# PCC_hat3.net
KiCad netlist of a schematic drawn in EAGLE
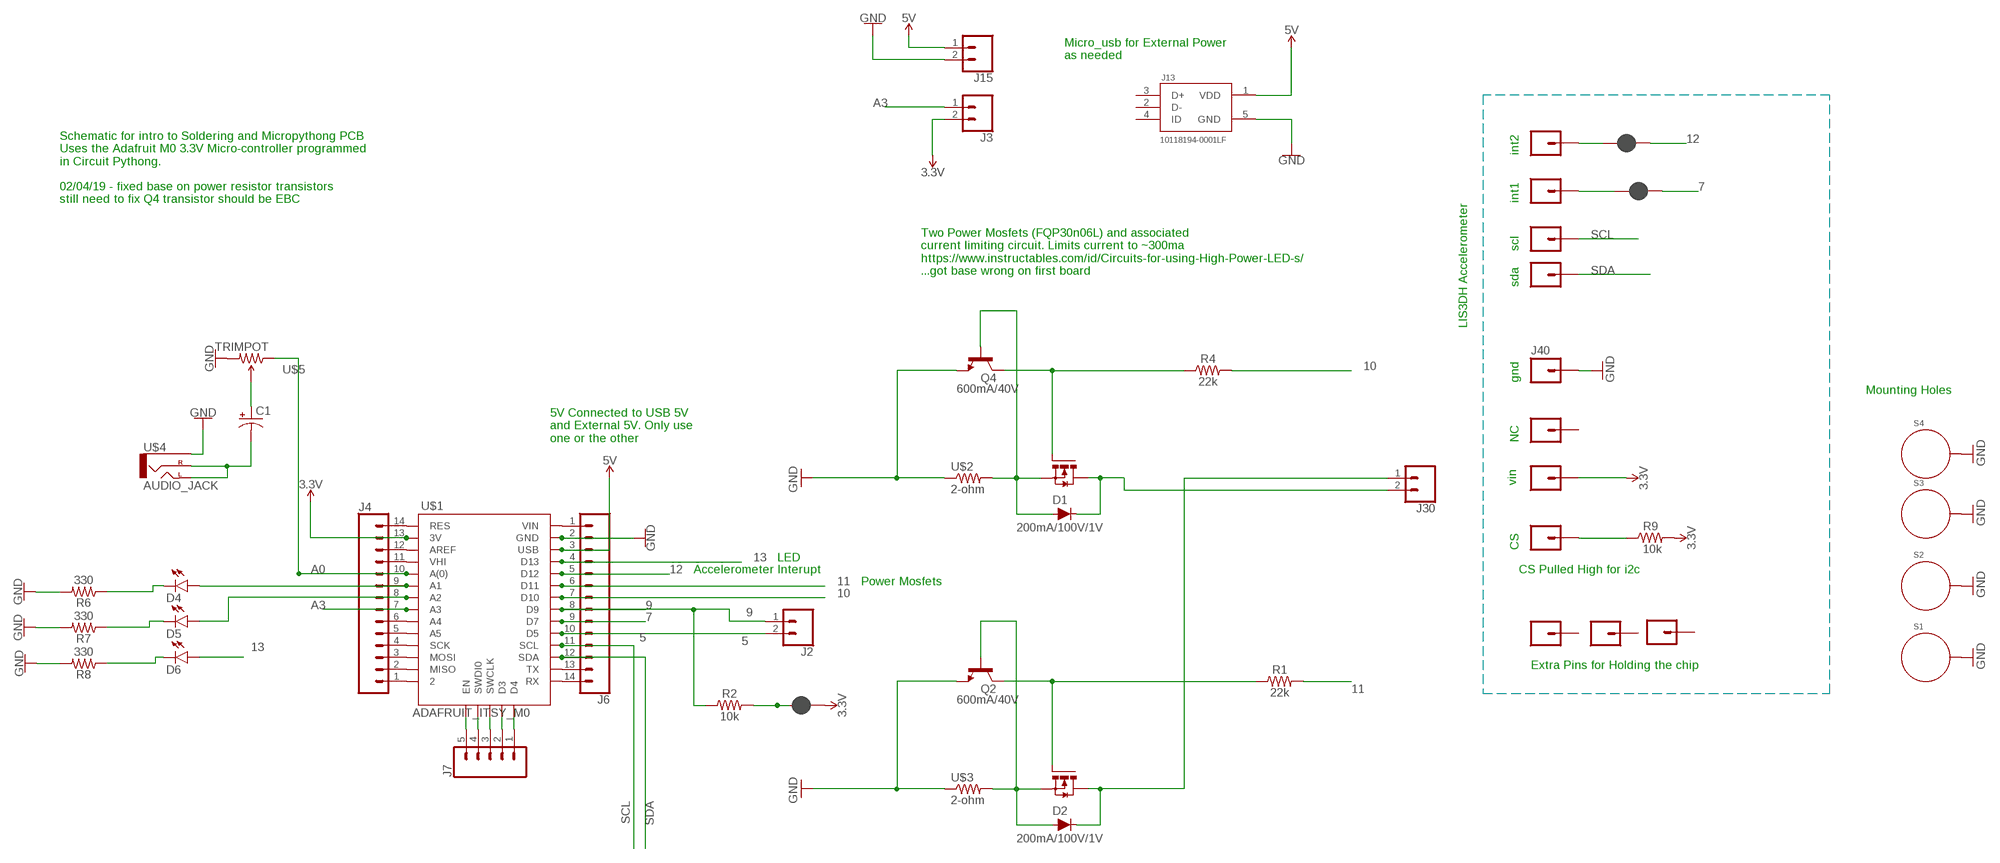
[diagram p0: schematic, sheet 1]

(export (version "E")
  (design (tool "Eeschema 10.0.6"))
  (components
    (comp (ref "C1")
      (value "CAP_POLPTH1")
      (footprint "eagle-import:CPOL-RADIAL-100UF-25V")
      (libsource (lib "eagle-import") (part "CAP_POLPTH1"))
    )
    (comp (ref "D1")
      (value "200mA/100V/1V")
      (footprint "eagle-import:DIODE-1N4148-KIT")
      (libsource (lib "eagle-import") (part "DIODE-KIT"))
    )
    (comp (ref "D2")
      (value "200mA/100V/1V")
      (footprint "eagle-import:DIODE-1N4148-KIT")
      (libsource (lib "eagle-import") (part "DIODE-KIT"))
    )
    (comp (ref "D4")
      (value "LED5MM")
      (footprint "eagle-import:LED5MM")
      (libsource (lib "eagle-import") (part "LED5MM"))
    )
    (comp (ref "D5")
      (value "LED5MM")
      (footprint "eagle-import:LED5MM")
      (libsource (lib "eagle-import") (part "LED5MM"))
    )
    (comp (ref "D6")
      (value "LED5MM")
      (footprint "eagle-import:LED5MM")
      (libsource (lib "eagle-import") (part "LED5MM"))
    )
    (comp (ref "J2")
      (value "CONN_025MM")
      (footprint "eagle-import:SCREWTERMINAL-5MM-2")
      (libsource (lib "eagle-import") (part "CONN_025MM"))
    )
    (comp (ref "J3")
      (value "CONN_025MM")
      (footprint "eagle-import:SCREWTERMINAL-5MM-2")
      (libsource (lib "eagle-import") (part "CONN_025MM"))
    )
    (comp (ref "J4")
      (value "CONN_14")
      (footprint "eagle-import:1X14")
      (libsource (lib "eagle-import") (part "CONN_14"))
    )
    (comp (ref "J5")
      (value "M01PTH")
      (footprint "eagle-import:1X01")
      (libsource (lib "eagle-import") (part "M01PTH"))
    )
    (comp (ref "J6")
      (value "CONN_14")
      (footprint "eagle-import:1X14")
      (libsource (lib "eagle-import") (part "CONN_14"))
    )
    (comp (ref "J7")
      (value "CONN_05")
      (footprint "eagle-import:1X05")
      (libsource (lib "eagle-import") (part "CONN_05"))
    )
    (comp (ref "J8")
      (value "M01PTH")
      (footprint "eagle-import:1X01")
      (libsource (lib "eagle-import") (part "M01PTH"))
    )
    (comp (ref "J9")
      (value "M01PTH")
      (footprint "eagle-import:1X01")
      (libsource (lib "eagle-import") (part "M01PTH"))
    )
    (comp (ref "J10")
      (value "M01PTH")
      (footprint "eagle-import:1X01")
      (libsource (lib "eagle-import") (part "M01PTH"))
    )
    (comp (ref "J11")
      (value "M01PTH")
      (footprint "eagle-import:1X01")
      (libsource (lib "eagle-import") (part "M01PTH"))
    )
    (comp (ref "J12")
      (value "M01PTH")
      (footprint "eagle-import:1X01")
      (libsource (lib "eagle-import") (part "M01PTH"))
    )
    (comp (ref "J13")
      (value "10118194-0001LF")
      (footprint "eagle-import:FRAMATOME_10118194-0001LF")
      (fields (field (name "MF") "Amphenol ICC"))
      (libsource (lib "eagle-import") (part "10118194-0001LF"))
    )
    (comp (ref "J15")
      (value "CONN_025MM")
      (footprint "eagle-import:SCREWTERMINAL-5MM-2")
      (libsource (lib "eagle-import") (part "CONN_025MM"))
    )
    (comp (ref "J30")
      (value "CONN_025MM")
      (footprint "eagle-import:SCREWTERMINAL-5MM-2")
      (libsource (lib "eagle-import") (part "CONN_025MM"))
    )
    (comp (ref "J39")
      (value "M01PTH")
      (footprint "eagle-import:1X01")
      (libsource (lib "eagle-import") (part "M01PTH"))
    )
    (comp (ref "J40")
      (value "M01PTH")
      (footprint "eagle-import:1X01")
      (libsource (lib "eagle-import") (part "M01PTH"))
    )
    (comp (ref "J42")
      (value "M01PTH")
      (footprint "eagle-import:1X01")
      (libsource (lib "eagle-import") (part "M01PTH"))
    )
    (comp (ref "J43")
      (value "M01PTH")
      (footprint "eagle-import:1X01")
      (libsource (lib "eagle-import") (part "M01PTH"))
    )
    (comp (ref "J44")
      (value "M01PTH")
      (footprint "eagle-import:1X01")
      (libsource (lib "eagle-import") (part "M01PTH"))
    )
    (comp (ref "JP1")
      (value "JUMPER-SMT_2_NC_PASTE_SILK")
      (footprint "eagle-import:SMT-JUMPER_2_NC_PASTE_SILK")
      (libsource (lib "eagle-import") (part "JUMPER-SMT_2_NC_PASTE_SILK"))
    )
    (comp (ref "JP2")
      (value "JUMPER-SMT_2_NC_PASTE_SILK")
      (footprint "eagle-import:SMT-JUMPER_2_NC_PASTE_SILK")
      (libsource (lib "eagle-import") (part "JUMPER-SMT_2_NC_PASTE_SILK"))
    )
    (comp (ref "JP3")
      (value "JUMPER-SMT_2_NC_PASTE_SILK")
      (footprint "eagle-import:SMT-JUMPER_2_NC_PASTE_SILK")
      (libsource (lib "eagle-import") (part "JUMPER-SMT_2_NC_PASTE_SILK"))
    )
    (comp (ref "Q1")
      (value "IRFI540NPBF")
      (footprint "eagle-import:TO220BH")
      (libsource (lib "eagle-import") (part "IRFI540NPBF"))
    )
    (comp (ref "Q2")
      (value "600mA/40V")
      (footprint "eagle-import:TO-92")
      (libsource (lib "eagle-import") (part "TRANS_NPN-P2N2222A"))
    )
    (comp (ref "Q3")
      (value "IRFI540NPBF")
      (footprint "eagle-import:TO220BH")
      (libsource (lib "eagle-import") (part "IRFI540NPBF"))
    )
    (comp (ref "Q4")
      (value "600mA/40V")
      (footprint "eagle-import:TO-92")
      (libsource (lib "eagle-import") (part "TRANS_NPN-P2N2222A"))
    )
    (comp (ref "R1")
      (value "22k")
      (footprint "eagle-import:AXIAL-0.3-KIT")
      (libsource (lib "eagle-import") (part "RESISTORAXIAL-0.3-KIT"))
    )
    (comp (ref "R2")
      (value "10k")
      (footprint "eagle-import:AXIAL-0.3-KIT")
      (libsource (lib "eagle-import") (part "RESISTORAXIAL-0.3-KIT"))
    )
    (comp (ref "R4")
      (value "22k")
      (footprint "eagle-import:AXIAL-0.3-KIT")
      (libsource (lib "eagle-import") (part "RESISTORAXIAL-0.3-KIT"))
    )
    (comp (ref "R6")
      (value "330")
      (footprint "eagle-import:AXIAL-0.3-KIT")
      (libsource (lib "eagle-import") (part "RESISTORAXIAL-0.3-KIT"))
    )
    (comp (ref "R7")
      (value "330")
      (footprint "eagle-import:AXIAL-0.3-KIT")
      (libsource (lib "eagle-import") (part "RESISTORAXIAL-0.3-KIT"))
    )
    (comp (ref "R8")
      (value "330")
      (footprint "eagle-import:AXIAL-0.3-KIT")
      (libsource (lib "eagle-import") (part "RESISTORAXIAL-0.3-KIT"))
    )
    (comp (ref "R9")
      (value "10k")
      (footprint "eagle-import:AXIAL-0.3-KIT")
      (libsource (lib "eagle-import") (part "RESISTORAXIAL-0.3-KIT"))
    )
    (comp (ref "S1")
      (value "STANDOFF_ELECTRICAL")
      (footprint "eagle-import:STANDOFF-ELECTRICAL")
      (fields (field (name "SPICEPREFIX") "X"))
      (libsource (lib "eagle-import") (part "STANDOFF_ELECTRICAL"))
    )
    (comp (ref "S2")
      (value "STANDOFF_ELECTRICAL")
      (footprint "eagle-import:STANDOFF-ELECTRICAL")
      (fields (field (name "SPICEPREFIX") "X"))
      (libsource (lib "eagle-import") (part "STANDOFF_ELECTRICAL"))
    )
    (comp (ref "S3")
      (value "STANDOFF_ELECTRICAL")
      (footprint "eagle-import:STANDOFF-ELECTRICAL")
      (fields (field (name "SPICEPREFIX") "X"))
      (libsource (lib "eagle-import") (part "STANDOFF_ELECTRICAL"))
    )
    (comp (ref "S4")
      (value "STANDOFF_ELECTRICAL")
      (footprint "eagle-import:STANDOFF-ELECTRICAL")
      (fields (field (name "SPICEPREFIX") "X"))
      (libsource (lib "eagle-import") (part "STANDOFF_ELECTRICAL"))
    )
    (comp (ref "U$1")
      (value "ADAFRUIT_ITSY_M0")
      (footprint "eagle-import:ADAFRUIT_ITS_M0")
      (libsource (lib "eagle-import") (part "ADAFRUIT_ITSY_M0"))
    )
    (comp (ref "U$2")
      (value "2-ohm")
      (footprint "eagle-import:RESISTOR_5W_PT")
      (libsource (lib "eagle-import") (part "RESISTOR"))
    )
    (comp (ref "U$3")
      (value "2-ohm")
      (footprint "eagle-import:RESISTOR_5W_PT")
      (libsource (lib "eagle-import") (part "RESISTOR"))
    )
    (comp (ref "U$4")
      (value "AUDIO_JACK")
      (footprint "eagle-import:1_8_AUDIO_JACK")
      (libsource (lib "eagle-import") (part "AUDIO_JACK"))
    )
    (comp (ref "U$5")
      (value "TRIMPOT")
      (footprint "eagle-import:1X03_TRIMPOT")
      (libsource (lib "eagle-import") (part "TRIMPOT"))
    )
  )
  (nets
    (net (code "1") (name "/5") (class "Default")
      (node (ref "J2") (pin "2") (pinfunction "2_2") (pintype "passive"))
      (node (ref "J6") (pin "10") (pinfunction "10_10") (pintype "passive"))
      (node (ref "U$1") (pin "D5") (pinfunction "D5_D5") (pintype "bidirectional"))
    )
    (net (code "2") (name "/7") (class "Default")
      (node (ref "J6") (pin "9") (pinfunction "9_9") (pintype "passive"))
      (node (ref "JP1") (pin "2") (pinfunction "2_2") (pintype "passive"))
      (node (ref "U$1") (pin "D7") (pinfunction "D7_D7") (pintype "bidirectional"))
    )
    (net (code "3") (name "/9") (class "Default")
      (node (ref "J2") (pin "1") (pinfunction "1_1") (pintype "passive"))
      (node (ref "J6") (pin "8") (pinfunction "8_8") (pintype "passive"))
      (node (ref "R2") (pin "P$1") (pinfunction "1_P$1") (pintype "passive"))
      (node (ref "U$1") (pin "D9") (pinfunction "D9_D9") (pintype "bidirectional"))
    )
    (net (code "4") (name "/10") (class "Default")
      (node (ref "J6") (pin "7") (pinfunction "7_7") (pintype "passive"))
      (node (ref "R4") (pin "P$2") (pinfunction "2_P$2") (pintype "passive"))
      (node (ref "U$1") (pin "D10") (pinfunction "D10_D10") (pintype "bidirectional"))
    )
    (net (code "5") (name "/11") (class "Default")
      (node (ref "J6") (pin "6") (pinfunction "6_6") (pintype "passive"))
      (node (ref "R1") (pin "P$2") (pinfunction "2_P$2") (pintype "passive"))
      (node (ref "U$1") (pin "D11") (pinfunction "D11_D11") (pintype "bidirectional"))
    )
    (net (code "6") (name "/12") (class "Default")
      (node (ref "J6") (pin "5") (pinfunction "5_5") (pintype "passive"))
      (node (ref "JP2") (pin "2") (pinfunction "2_2") (pintype "passive"))
      (node (ref "U$1") (pin "D12") (pinfunction "D12_D12") (pintype "bidirectional"))
    )
    (net (code "7") (name "/13") (class "Default")
      (node (ref "D6") (pin "A") (pinfunction "A_A") (pintype "passive"))
      (node (ref "J6") (pin "4") (pinfunction "4_4") (pintype "passive"))
      (node (ref "U$1") (pin "D13") (pinfunction "D13_D13") (pintype "bidirectional"))
    )
    (net (code "8") (name "/A0") (class "Default")
      (node (ref "J4") (pin "10") (pinfunction "10_10") (pintype "passive"))
      (node (ref "U$1") (pin "A0") (pinfunction "A(0)_A0") (pintype "bidirectional"))
      (node (ref "U$5") (pin "1") (pinfunction "CCW_1") (pintype "passive"))
    )
    (net (code "9") (name "/A3") (class "Default")
      (node (ref "J3") (pin "1") (pinfunction "1_1") (pintype "passive"))
      (node (ref "J4") (pin "7") (pinfunction "7_7") (pintype "passive"))
      (node (ref "U$1") (pin "A3") (pinfunction "A3_A3") (pintype "bidirectional"))
    )
    (net (code "10") (name "/SCL") (class "Default")
      (node (ref "J43") (pin "1") (pinfunction "1_1") (pintype "passive"))
      (node (ref "J6") (pin "11") (pinfunction "11_11") (pintype "passive"))
      (node (ref "U$1") (pin "SCL") (pinfunction "SCL_SCL") (pintype "bidirectional"))
    )
    (net (code "11") (name "/SDA") (class "Default")
      (node (ref "J42") (pin "1") (pinfunction "1_1") (pintype "passive"))
      (node (ref "J6") (pin "12") (pinfunction "12_12") (pintype "passive"))
      (node (ref "U$1") (pin "SDA") (pinfunction "SDA_SDA") (pintype "bidirectional"))
    )
    (net (code "12") (name "3.3V") (class "Default")
      (node (ref "J3") (pin "2") (pinfunction "2_2") (pintype "passive"))
      (node (ref "J4") (pin "13") (pinfunction "13_13") (pintype "passive"))
      (node (ref "J5") (pin "1") (pinfunction "1_1") (pintype "passive"))
      (node (ref "JP3") (pin "2") (pinfunction "2_2") (pintype "passive"))
      (node (ref "R9") (pin "P$2") (pinfunction "2_P$2") (pintype "passive"))
      (node (ref "U$1") (pin "3V") (pinfunction "3V_3V") (pintype "bidirectional"))
    )
    (net (code "13") (name "5V") (class "Default")
      (node (ref "J13") (pin "1") (pinfunction "VDD_1") (pintype "power_in"))
      (node (ref "J15") (pin "1") (pinfunction "1_1") (pintype "passive"))
      (node (ref "J6") (pin "3") (pinfunction "3_3") (pintype "passive"))
      (node (ref "U$1") (pin "USB") (pinfunction "USB_USB") (pintype "bidirectional"))
    )
    (net (code "14") (name "GND") (class "Default")
      (node (ref "J13") (pin "5") (pinfunction "GND_5") (pintype "power_in"))
      (node (ref "J15") (pin "2") (pinfunction "2_2") (pintype "passive"))
      (node (ref "J40") (pin "1") (pinfunction "1_1") (pintype "passive"))
      (node (ref "J6") (pin "2") (pinfunction "2_2") (pintype "passive"))
      (node (ref "Q2") (pin "3") (pinfunction "E_3") (pintype "passive"))
      (node (ref "Q4") (pin "3") (pinfunction "E_3") (pintype "passive"))
      (node (ref "R6") (pin "P$2") (pinfunction "2_P$2") (pintype "passive"))
      (node (ref "R7") (pin "P$2") (pinfunction "2_P$2") (pintype "passive"))
      (node (ref "R8") (pin "P$2") (pinfunction "2_P$2") (pintype "passive"))
      (node (ref "S1") (pin "P1") (pinfunction "P$1_P1") (pintype "bidirectional"))
      (node (ref "S2") (pin "P1") (pinfunction "P$1_P1") (pintype "bidirectional"))
      (node (ref "S3") (pin "P1") (pinfunction "P$1_P1") (pintype "bidirectional"))
      (node (ref "S4") (pin "P1") (pinfunction "P$1_P1") (pintype "bidirectional"))
      (node (ref "U$1") (pin "GND") (pinfunction "GND_GND") (pintype "bidirectional"))
      (node (ref "U$2") (pin "P$1") (pinfunction "1_P$1") (pintype "passive"))
      (node (ref "U$3") (pin "P$1") (pinfunction "1_P$1") (pintype "passive"))
      (node (ref "U$4") (pin "GND") (pinfunction "SLEEVE_GND") (pintype "bidirectional"))
      (node (ref "U$5") (pin "3") (pinfunction "CW_3") (pintype "passive"))
    )
    (net (code "15") (name "Net-(C1-+)") (class "Default")
      (node (ref "C1") (pin "1") (pinfunction "+_1") (pintype "passive"))
      (node (ref "U$5") (pin "2") (pinfunction "WIPER_2") (pintype "passive"))
    )
    (net (code "16") (name "Net-(C1--)") (class "Default")
      (node (ref "C1") (pin "2") (pinfunction "-_2") (pintype "passive"))
      (node (ref "U$4") (pin "LEFT_TIP_1") (pinfunction "LEFT_LEFT_TIP_1") (pintype "bidirectional"))
      (node (ref "U$4") (pin "RIGHT") (pinfunction "RIGHT_RIGHT") (pintype "bidirectional"))
    )
    (net (code "17") (name "Net-(D1-PadC)") (class "Default")
      (node (ref "D1") (pin "C") (pinfunction "C_C") (pintype "passive"))
      (node (ref "J30") (pin "2") (pinfunction "2_2") (pintype "passive"))
      (node (ref "Q3") (pin "D") (pinfunction "D_D") (pintype "passive"))
    )
    (net (code "18") (name "Net-(D2-PadC)") (class "Default")
      (node (ref "D2") (pin "C") (pinfunction "C_C") (pintype "passive"))
      (node (ref "J30") (pin "1") (pinfunction "1_1") (pintype "passive"))
      (node (ref "Q1") (pin "D") (pinfunction "D_D") (pintype "passive"))
    )
    (net (code "19") (name "Net-(D4-C)") (class "Default")
      (node (ref "D4") (pin "K") (pinfunction "C_K") (pintype "passive"))
      (node (ref "R6") (pin "P$1") (pinfunction "1_P$1") (pintype "passive"))
    )
    (net (code "20") (name "Net-(D4-PadA)") (class "Default")
      (node (ref "D4") (pin "A") (pinfunction "A_A") (pintype "passive"))
      (node (ref "J4") (pin "9") (pinfunction "9_9") (pintype "passive"))
      (node (ref "U$1") (pin "A1") (pinfunction "A1_A1") (pintype "bidirectional"))
    )
    (net (code "21") (name "Net-(D5-C)") (class "Default")
      (node (ref "D5") (pin "K") (pinfunction "C_K") (pintype "passive"))
      (node (ref "R7") (pin "P$1") (pinfunction "1_P$1") (pintype "passive"))
    )
    (net (code "22") (name "Net-(D5-PadA)") (class "Default")
      (node (ref "D5") (pin "A") (pinfunction "A_A") (pintype "passive"))
      (node (ref "J4") (pin "8") (pinfunction "8_8") (pintype "passive"))
      (node (ref "U$1") (pin "A2") (pinfunction "A2_A2") (pintype "bidirectional"))
    )
    (net (code "23") (name "Net-(D6-C)") (class "Default")
      (node (ref "D6") (pin "K") (pinfunction "C_K") (pintype "passive"))
      (node (ref "R8") (pin "P$1") (pinfunction "1_P$1") (pintype "passive"))
    )
    (net (code "24") (name "Net-(J4-Pad1)") (class "Default")
      (node (ref "J4") (pin "1") (pinfunction "1_1") (pintype "passive"))
      (node (ref "U$1") (pin "2") (pinfunction "2_2") (pintype "bidirectional"))
    )
    (net (code "25") (name "Net-(J4-Pad2)") (class "Default")
      (node (ref "J4") (pin "2") (pinfunction "2_2") (pintype "passive"))
      (node (ref "U$1") (pin "MISO") (pinfunction "MISO_MISO") (pintype "bidirectional"))
    )
    (net (code "26") (name "Net-(J4-Pad3)") (class "Default")
      (node (ref "J4") (pin "3") (pinfunction "3_3") (pintype "passive"))
      (node (ref "U$1") (pin "MOSI") (pinfunction "MOSI_MOSI") (pintype "bidirectional"))
    )
    (net (code "27") (name "Net-(J4-Pad4)") (class "Default")
      (node (ref "J4") (pin "4") (pinfunction "4_4") (pintype "passive"))
      (node (ref "U$1") (pin "SCK") (pinfunction "SCK_SCK") (pintype "bidirectional"))
    )
    (net (code "28") (name "Net-(J4-Pad5)") (class "Default")
      (node (ref "J4") (pin "5") (pinfunction "5_5") (pintype "passive"))
      (node (ref "U$1") (pin "A5") (pinfunction "A5_A5") (pintype "bidirectional"))
    )
    (net (code "29") (name "Net-(J4-Pad6)") (class "Default")
      (node (ref "J4") (pin "6") (pinfunction "6_6") (pintype "passive"))
      (node (ref "U$1") (pin "A4") (pinfunction "A4_A4") (pintype "bidirectional"))
    )
    (net (code "30") (name "Net-(J4-Pad11)") (class "Default")
      (node (ref "J4") (pin "11") (pinfunction "11_11") (pintype "passive"))
      (node (ref "U$1") (pin "VHI") (pinfunction "VHI_VHI") (pintype "bidirectional"))
    )
    (net (code "31") (name "Net-(J4-Pad12)") (class "Default")
      (node (ref "J4") (pin "12") (pinfunction "12_12") (pintype "passive"))
      (node (ref "U$1") (pin "AREF") (pinfunction "AREF_AREF") (pintype "bidirectional"))
    )
    (net (code "32") (name "Net-(J4-Pad14)") (class "Default")
      (node (ref "J4") (pin "14") (pinfunction "14_14") (pintype "passive"))
      (node (ref "U$1") (pin "RES") (pinfunction "RES_RES") (pintype "bidirectional"))
    )
    (net (code "33") (name "Net-(J6-Pad1)") (class "Default")
      (node (ref "J6") (pin "1") (pinfunction "1_1") (pintype "passive"))
      (node (ref "U$1") (pin "VIN") (pinfunction "VIN_VIN") (pintype "bidirectional"))
    )
    (net (code "34") (name "Net-(J6-Pad13)") (class "Default")
      (node (ref "J6") (pin "13") (pinfunction "13_13") (pintype "passive"))
      (node (ref "U$1") (pin "TX") (pinfunction "TX_TX") (pintype "bidirectional"))
    )
    (net (code "35") (name "Net-(J6-Pad14)") (class "Default")
      (node (ref "J6") (pin "14") (pinfunction "14_14") (pintype "passive"))
      (node (ref "U$1") (pin "RX") (pinfunction "RX_RX") (pintype "bidirectional"))
    )
    (net (code "36") (name "Net-(J7-Pad1)") (class "Default")
      (node (ref "J7") (pin "1") (pinfunction "1_1") (pintype "passive"))
      (node (ref "U$1") (pin "D4") (pinfunction "D4_D4") (pintype "bidirectional"))
    )
    (net (code "37") (name "Net-(J7-Pad3)") (class "Default")
      (node (ref "J7") (pin "3") (pinfunction "3_3") (pintype "passive"))
      (node (ref "U$1") (pin "SWCLK") (pinfunction "SWCLK_SWCLK") (pintype "bidirectional"))
    )
    (net (code "38") (name "Net-(J7-Pad4)") (class "Default")
      (node (ref "J7") (pin "4") (pinfunction "4_4") (pintype "passive"))
      (node (ref "U$1") (pin "SWDI0") (pinfunction "SWDI0_SWDI0") (pintype "bidirectional"))
    )
    (net (code "39") (name "Net-(J7-Pad5)") (class "Default")
      (node (ref "J7") (pin "5") (pinfunction "5_5") (pintype "passive"))
      (node (ref "U$1") (pin "EN") (pinfunction "EN_EN") (pintype "bidirectional"))
    )
    (net (code "40") (name "Net-(J11-Pad1)") (class "Default")
      (node (ref "J11") (pin "1") (pinfunction "1_1") (pintype "passive"))
      (node (ref "JP2") (pin "1") (pinfunction "1_1") (pintype "passive"))
    )
    (net (code "41") (name "Net-(J44-Pad1)") (class "Default")
      (node (ref "J44") (pin "1") (pinfunction "1_1") (pintype "passive"))
      (node (ref "JP1") (pin "1") (pinfunction "1_1") (pintype "passive"))
    )
    (net (code "42") (name "Net-(Q2-B)") (class "Default")
      (node (ref "D2") (pin "A") (pinfunction "A_A") (pintype "passive"))
      (node (ref "Q1") (pin "S") (pinfunction "S_S") (pintype "passive"))
      (node (ref "Q2") (pin "2") (pinfunction "B_2") (pintype "passive"))
      (node (ref "U$3") (pin "P$2") (pinfunction "2_P$2") (pintype "passive"))
    )
    (net (code "43") (name "Net-(Q2-C)") (class "Default")
      (node (ref "Q1") (pin "G") (pinfunction "G_G") (pintype "passive"))
      (node (ref "Q2") (pin "1") (pinfunction "C_1") (pintype "passive"))
      (node (ref "R1") (pin "P$1") (pinfunction "1_P$1") (pintype "passive"))
    )
    (net (code "44") (name "Net-(Q4-B)") (class "Default")
      (node (ref "D1") (pin "A") (pinfunction "A_A") (pintype "passive"))
      (node (ref "Q3") (pin "S") (pinfunction "S_S") (pintype "passive"))
      (node (ref "Q4") (pin "2") (pinfunction "B_2") (pintype "passive"))
      (node (ref "U$2") (pin "P$2") (pinfunction "2_P$2") (pintype "passive"))
    )
    (net (code "45") (name "Net-(Q4-C)") (class "Default")
      (node (ref "Q3") (pin "G") (pinfunction "G_G") (pintype "passive"))
      (node (ref "Q4") (pin "1") (pinfunction "C_1") (pintype "passive"))
      (node (ref "R4") (pin "P$1") (pinfunction "1_P$1") (pintype "passive"))
    )
    (net (code "46") (name "Net-(R2-2)") (class "Default")
      (node (ref "JP3") (pin "1") (pinfunction "1_1") (pintype "passive"))
      (node (ref "R2") (pin "P$2") (pinfunction "2_P$2") (pintype "passive"))
    )
    (net (code "47") (name "Net-(R9-1)") (class "Default")
      (node (ref "J8") (pin "1") (pinfunction "1_1") (pintype "passive"))
      (node (ref "R9") (pin "P$1") (pinfunction "1_P$1") (pintype "passive"))
    )
    (net (code "48") (name "Net-(U$1-D3)") (class "Default")
      (node (ref "J7") (pin "2") (pinfunction "2_2") (pintype "passive"))
      (node (ref "U$1") (pin "3") (pinfunction "D3_3") (pintype "bidirectional"))
    )
    (net (code "49") (name "unconnected-(J9-Pad1)") (class "Default")
      (node (ref "J9") (pin "1") (pinfunction "1_1") (pintype "passive"))
    )
    (net (code "50") (name "unconnected-(J10-Pad1)") (class "Default")
      (node (ref "J10") (pin "1") (pinfunction "1_1") (pintype "passive"))
    )
    (net (code "51") (name "unconnected-(J12-Pad1)") (class "Default")
      (node (ref "J12") (pin "1") (pinfunction "1_1") (pintype "passive"))
    )
    (net (code "52") (name "unconnected-(J13-D+-Pad3)") (class "Default")
      (node (ref "J13") (pin "3") (pinfunction "D+_3") (pintype "bidirectional"))
    )
    (net (code "53") (name "unconnected-(J13-D--Pad2)") (class "Default")
      (node (ref "J13") (pin "2") (pinfunction "D-_2") (pintype "bidirectional"))
    )
    (net (code "54") (name "unconnected-(J13-ID-Pad4)") (class "Default")
      (node (ref "J13") (pin "4") (pinfunction "ID_4") (pintype "passive"))
    )
    (net (code "55") (name "unconnected-(J39-Pad1)") (class "Default")
      (node (ref "J39") (pin "1") (pinfunction "1_1") (pintype "passive"))
    )
  )
)
